# ArduinoMegaShield3.net
KiCad netlist of a schematic drawn in EAGLE
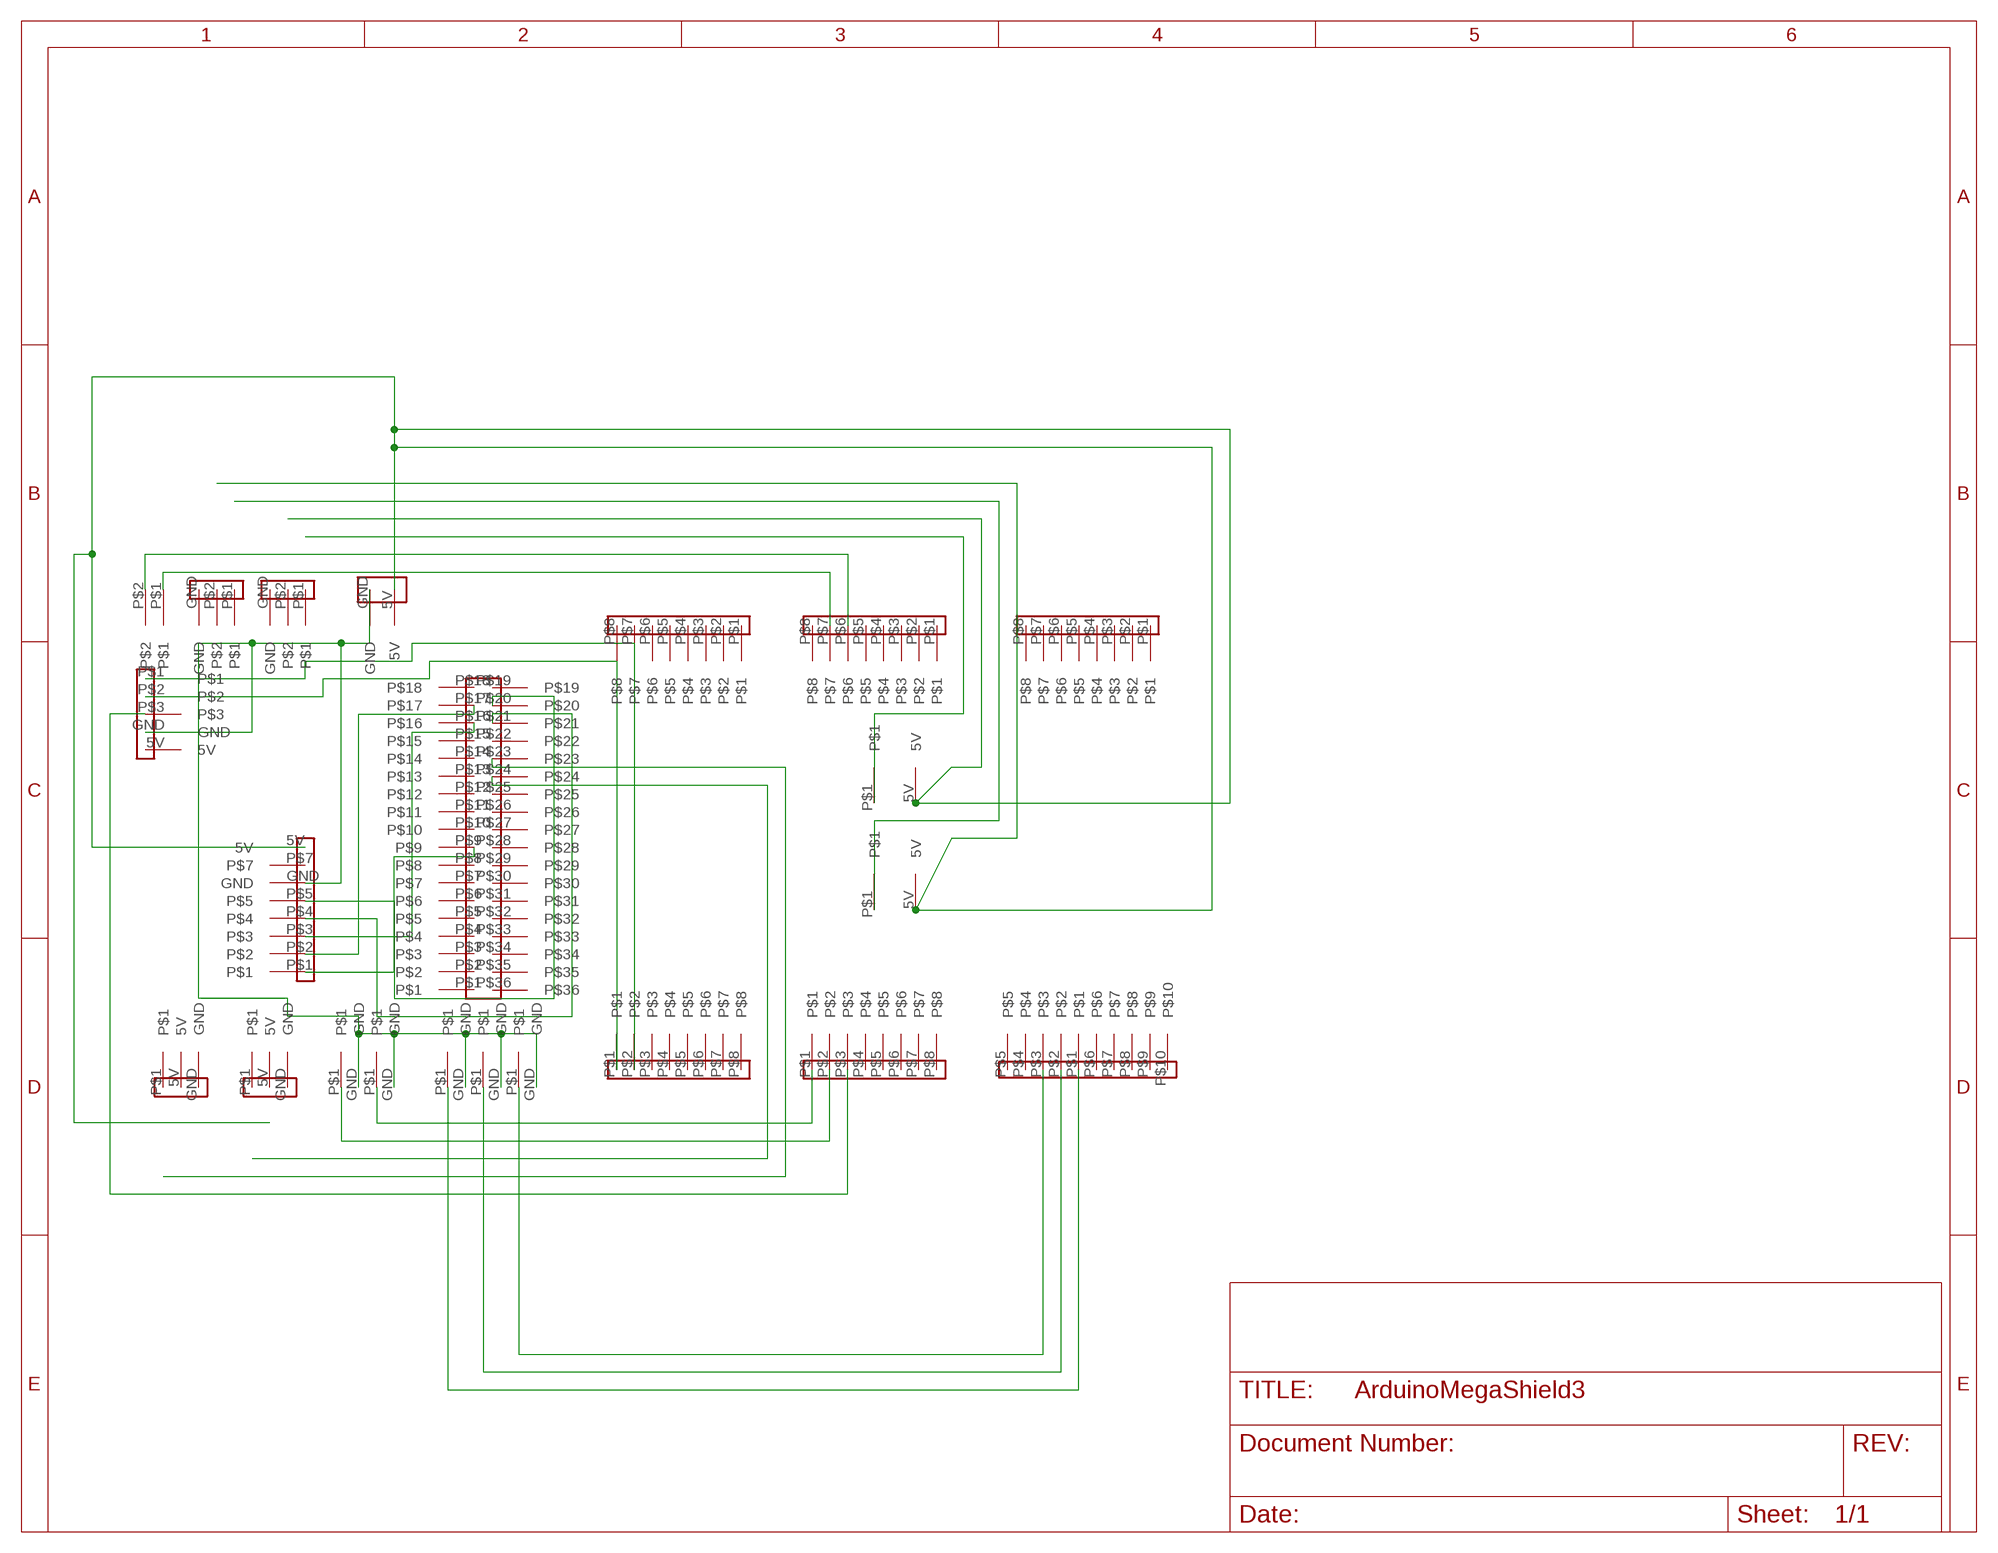
[diagram p0: schematic, sheet 1]

(export (version "E")
  (design (tool "Eeschema 10.0.6"))
  (components
    (comp (ref "U$1")
      (value "8PINHEADER2.54MM")
      (footprint "eagle-import:8PINHEADER2.54MM")
      (libsource (lib "eagle-import") (part "8PINHEADER2.54MM"))
    )
    (comp (ref "U$2")
      (value "8PINHEADER2.54MM")
      (footprint "eagle-import:8PINHEADER2.54MM")
      (libsource (lib "eagle-import") (part "8PINHEADER2.54MM"))
    )
    (comp (ref "U$3")
      (value "8PINHEADER2.54MM")
      (footprint "eagle-import:8PINHEADER2.54MM")
      (libsource (lib "eagle-import") (part "8PINHEADER2.54MM"))
    )
    (comp (ref "U$4")
      (value "8PINHEADER2.54MM")
      (footprint "eagle-import:8PINHEADER2.54MM")
      (libsource (lib "eagle-import") (part "8PINHEADER2.54MM"))
    )
    (comp (ref "U$5")
      (value "8PINHEADER2.54MM")
      (footprint "eagle-import:8PINHEADER2.54MM")
      (libsource (lib "eagle-import") (part "8PINHEADER2.54MM"))
    )
    (comp (ref "U$6")
      (value "10PINHEADER2.54MM")
      (footprint "eagle-import:10PINHEADER2.54MM")
      (libsource (lib "eagle-import") (part "10PINHEADER2.54MM"))
    )
    (comp (ref "U$7")
      (value "18X2HEADER2.54MM")
      (footprint "eagle-import:18X2HEADER2.54MM")
      (libsource (lib "eagle-import") (part "18X2HEADER2.54MM"))
    )
    (comp (ref "U$8")
      (value "5PINHEADER2.54MM")
      (footprint "eagle-import:5PINHEADER2.54MM")
      (libsource (lib "eagle-import") (part "5PINHEADER2.54MM"))
    )
    (comp (ref "U$9")
      (value "SERVOS")
      (footprint "eagle-import:SERVOS")
      (libsource (lib "eagle-import") (part "SERVOS"))
    )
    (comp (ref "U$10")
      (value "SDCARDMODULE")
      (footprint "eagle-import:SDCARDMODULE")
      (libsource (lib "eagle-import") (part "SDCARDMODULE"))
    )
    (comp (ref "U$11")
      (value "SERVOS")
      (footprint "eagle-import:SERVOS")
      (libsource (lib "eagle-import") (part "SERVOS"))
    )
    (comp (ref "U$12")
      (value "HALLEFFECTSENSORS")
      (footprint "eagle-import:HALLEFFECTSENSORS")
      (libsource (lib "eagle-import") (part "HALLEFFECTSENSORS"))
    )
    (comp (ref "U$13")
      (value "HALLEFFECTSENSORS")
      (footprint "eagle-import:HALLEFFECTSENSORS")
      (libsource (lib "eagle-import") (part "HALLEFFECTSENSORS"))
    )
    (comp (ref "U$14")
      (value "2PIN2.54MM")
      (footprint "eagle-import:2PIN2.54MM")
      (libsource (lib "eagle-import") (part "2PIN2.54MM"))
    )
    (comp (ref "U$15")
      (value "2PIN2.54MM")
      (footprint "eagle-import:2PIN2.54MM")
      (libsource (lib "eagle-import") (part "2PIN2.54MM"))
    )
    (comp (ref "U$17")
      (value "2PIN2.54MM")
      (footprint "eagle-import:2PIN2.54MM")
      (libsource (lib "eagle-import") (part "2PIN2.54MM"))
    )
    (comp (ref "U$18")
      (value "2PIN2.54MM")
      (footprint "eagle-import:2PIN2.54MM")
      (libsource (lib "eagle-import") (part "2PIN2.54MM"))
    )
    (comp (ref "U$19")
      (value "2PIN2.54MM")
      (footprint "eagle-import:2PIN2.54MM")
      (libsource (lib "eagle-import") (part "2PIN2.54MM"))
    )
    (comp (ref "U$20")
      (value "2PIN11MM")
      (footprint "eagle-import:2PIN11MM")
      (libsource (lib "eagle-import") (part "2PIN11MM"))
    )
    (comp (ref "U$21")
      (value "2PIN11MM")
      (footprint "eagle-import:2PIN11MM")
      (libsource (lib "eagle-import") (part "2PIN11MM"))
    )
    (comp (ref "U$22")
      (value "BUTTONS")
      (footprint "eagle-import:BUTTONS")
      (libsource (lib "eagle-import") (part "BUTTONS"))
    )
    (comp (ref "U$23")
      (value "2PINTERMINAL3.5MM")
      (footprint "eagle-import:2PINTERMINAL3.5MM")
      (libsource (lib "eagle-import") (part "2PINTERMINAL3.5MM"))
    )
  )
  (nets
    (net (code "1") (name "Net-(U$1-PadP$1)") (class "Default")
      (node (ref "U$1") (pin "P$1") (pinfunction "P$1_P$1") (pintype "bidirectional"))
      (node (ref "U$15") (pin "P$1") (pinfunction "P$1_P$1") (pintype "bidirectional"))
    )
    (net (code "2") (name "Net-(U$1-PadP$2)") (class "Default")
      (node (ref "U$1") (pin "P$2") (pinfunction "P$2_P$2") (pintype "bidirectional"))
      (node (ref "U$14") (pin "P$1") (pinfunction "P$1_P$1") (pintype "bidirectional"))
    )
    (net (code "3") (name "Net-(U$1-PadP$3)") (class "Default")
      (node (ref "U$1") (pin "P$3") (pinfunction "P$3_P$3") (pintype "bidirectional"))
      (node (ref "U$8") (pin "P$3") (pinfunction "P$3_P$3") (pintype "bidirectional"))
    )
    (net (code "4") (name "Net-(U$2-PadP$1)") (class "Default")
      (node (ref "U$2") (pin "P$1") (pinfunction "P$1_P$1") (pintype "bidirectional"))
      (node (ref "U$8") (pin "P$2") (pinfunction "P$2_P$2") (pintype "bidirectional"))
    )
    (net (code "5") (name "Net-(U$2-PadP$2)") (class "Default")
      (node (ref "U$2") (pin "P$2") (pinfunction "P$2_P$2") (pintype "bidirectional"))
      (node (ref "U$8") (pin "P$1") (pinfunction "P$1_P$1") (pintype "bidirectional"))
    )
    (net (code "6") (name "Net-(U$10-Pad5V)") (class "Default")
      (node (ref "U$10") (pin "5V") (pinfunction "5V_5V") (pintype "bidirectional"))
      (node (ref "U$20") (pin "5V") (pinfunction "5V_5V") (pintype "bidirectional"))
      (node (ref "U$21") (pin "5V") (pinfunction "5V_5V") (pintype "bidirectional"))
      (node (ref "U$23") (pin "5V") (pinfunction "5V_5V") (pintype "bidirectional"))
    )
    (net (code "7") (name "Net-(U$10-PadGND)") (class "Default")
      (node (ref "U$10") (pin "GND") (pinfunction "GND_GND") (pintype "bidirectional"))
      (node (ref "U$14") (pin "GND") (pinfunction "GND_GND") (pintype "bidirectional"))
      (node (ref "U$15") (pin "GND") (pinfunction "GND_GND") (pintype "bidirectional"))
      (node (ref "U$17") (pin "GND") (pinfunction "GND_GND") (pintype "bidirectional"))
      (node (ref "U$18") (pin "GND") (pinfunction "GND_GND") (pintype "bidirectional"))
      (node (ref "U$19") (pin "GND") (pinfunction "GND_GND") (pintype "bidirectional"))
      (node (ref "U$23") (pin "GND") (pinfunction "GND_GND") (pintype "bidirectional"))
      (node (ref "U$8") (pin "GND") (pinfunction "GND_GND") (pintype "bidirectional"))
    )
    (net (code "8") (name "Net-(U$10-PadP$1)") (class "Default")
      (node (ref "U$10") (pin "P$1") (pinfunction "P$1_P$1") (pintype "bidirectional"))
      (node (ref "U$7") (pin "P$9") (pinfunction "P$9_P$9") (pintype "bidirectional"))
    )
    (net (code "9") (name "Net-(U$10-PadP$2)") (class "Default")
      (node (ref "U$10") (pin "P$2") (pinfunction "P$2_P$2") (pintype "bidirectional"))
      (node (ref "U$7") (pin "P$17") (pinfunction "P$17_P$17") (pintype "bidirectional"))
    )
    (net (code "10") (name "Net-(U$10-PadP$3)") (class "Default")
      (node (ref "U$10") (pin "P$3") (pinfunction "P$3_P$3") (pintype "bidirectional"))
      (node (ref "U$7") (pin "P$16") (pinfunction "P$16_P$16") (pintype "bidirectional"))
    )
    (net (code "11") (name "Net-(U$10-PadP$4)") (class "Default")
      (node (ref "U$10") (pin "P$4") (pinfunction "P$4_P$4") (pintype "bidirectional"))
      (node (ref "U$7") (pin "P$21") (pinfunction "P$21_P$21") (pintype "bidirectional"))
    )
    (net (code "12") (name "Net-(U$10-PadP$5)") (class "Default")
      (node (ref "U$10") (pin "P$5") (pinfunction "P$5_P$5") (pintype "bidirectional"))
      (node (ref "U$7") (pin "P$20") (pinfunction "P$20_P$20") (pintype "bidirectional"))
    )
    (net (code "13") (name "Net-(U$17-PadP$1)") (class "Default")
      (node (ref "U$17") (pin "P$1") (pinfunction "P$1_P$1") (pintype "bidirectional"))
      (node (ref "U$6") (pin "P$1") (pinfunction "P$1_P$1") (pintype "bidirectional"))
    )
    (net (code "14") (name "Net-(U$18-PadP$1)") (class "Default")
      (node (ref "U$18") (pin "P$1") (pinfunction "P$1_P$1") (pintype "bidirectional"))
      (node (ref "U$6") (pin "P$2") (pinfunction "P$2_P$2") (pintype "bidirectional"))
    )
    (net (code "15") (name "Net-(U$19-PadP$1)") (class "Default")
      (node (ref "U$19") (pin "P$1") (pinfunction "P$1_P$1") (pintype "bidirectional"))
      (node (ref "U$6") (pin "P$3") (pinfunction "P$3_P$3") (pintype "bidirectional"))
    )
    (net (code "16") (name "Net-(U$22-PadP$1)") (class "Default")
      (node (ref "U$22") (pin "P$1") (pinfunction "P$1_P$1") (pintype "bidirectional"))
      (node (ref "U$4") (pin "P$7") (pinfunction "P$7_P$7") (pintype "bidirectional"))
    )
    (net (code "17") (name "Net-(U$22-PadP$2)") (class "Default")
      (node (ref "U$22") (pin "P$2") (pinfunction "P$2_P$2") (pintype "bidirectional"))
      (node (ref "U$4") (pin "P$6") (pinfunction "P$6_P$6") (pintype "bidirectional"))
    )
    (net (code "18") (name "unconnected-(U$1-PadP$4)") (class "Default")
      (node (ref "U$1") (pin "P$4") (pinfunction "P$4_P$4") (pintype "bidirectional"))
    )
    (net (code "19") (name "unconnected-(U$1-PadP$5)") (class "Default")
      (node (ref "U$1") (pin "P$5") (pinfunction "P$5_P$5") (pintype "bidirectional"))
    )
    (net (code "20") (name "unconnected-(U$1-PadP$6)") (class "Default")
      (node (ref "U$1") (pin "P$6") (pinfunction "P$6_P$6") (pintype "bidirectional"))
    )
    (net (code "21") (name "unconnected-(U$1-PadP$7)") (class "Default")
      (node (ref "U$1") (pin "P$7") (pinfunction "P$7_P$7") (pintype "bidirectional"))
    )
    (net (code "22") (name "unconnected-(U$1-PadP$8)") (class "Default")
      (node (ref "U$1") (pin "P$8") (pinfunction "P$8_P$8") (pintype "bidirectional"))
    )
    (net (code "23") (name "unconnected-(U$2-PadP$3)") (class "Default")
      (node (ref "U$2") (pin "P$3") (pinfunction "P$3_P$3") (pintype "bidirectional"))
    )
    (net (code "24") (name "unconnected-(U$2-PadP$4)") (class "Default")
      (node (ref "U$2") (pin "P$4") (pinfunction "P$4_P$4") (pintype "bidirectional"))
    )
    (net (code "25") (name "unconnected-(U$2-PadP$5)") (class "Default")
      (node (ref "U$2") (pin "P$5") (pinfunction "P$5_P$5") (pintype "bidirectional"))
    )
    (net (code "26") (name "unconnected-(U$2-PadP$6)") (class "Default")
      (node (ref "U$2") (pin "P$6") (pinfunction "P$6_P$6") (pintype "bidirectional"))
    )
    (net (code "27") (name "unconnected-(U$2-PadP$7)") (class "Default")
      (node (ref "U$2") (pin "P$7") (pinfunction "P$7_P$7") (pintype "bidirectional"))
    )
    (net (code "28") (name "unconnected-(U$2-PadP$8)") (class "Default")
      (node (ref "U$2") (pin "P$8") (pinfunction "P$8_P$8") (pintype "bidirectional"))
    )
    (net (code "29") (name "unconnected-(U$3-PadP$1)") (class "Default")
      (node (ref "U$3") (pin "P$1") (pinfunction "P$1_P$1") (pintype "bidirectional"))
    )
    (net (code "30") (name "unconnected-(U$3-PadP$2)") (class "Default")
      (node (ref "U$3") (pin "P$2") (pinfunction "P$2_P$2") (pintype "bidirectional"))
    )
    (net (code "31") (name "unconnected-(U$3-PadP$3)") (class "Default")
      (node (ref "U$3") (pin "P$3") (pinfunction "P$3_P$3") (pintype "bidirectional"))
    )
    (net (code "32") (name "unconnected-(U$3-PadP$4)") (class "Default")
      (node (ref "U$3") (pin "P$4") (pinfunction "P$4_P$4") (pintype "bidirectional"))
    )
    (net (code "33") (name "unconnected-(U$3-PadP$5)") (class "Default")
      (node (ref "U$3") (pin "P$5") (pinfunction "P$5_P$5") (pintype "bidirectional"))
    )
    (net (code "34") (name "unconnected-(U$3-PadP$6)") (class "Default")
      (node (ref "U$3") (pin "P$6") (pinfunction "P$6_P$6") (pintype "bidirectional"))
    )
    (net (code "35") (name "unconnected-(U$3-PadP$7)") (class "Default")
      (node (ref "U$3") (pin "P$7") (pinfunction "P$7_P$7") (pintype "bidirectional"))
    )
    (net (code "36") (name "unconnected-(U$3-PadP$8)") (class "Default")
      (node (ref "U$3") (pin "P$8") (pinfunction "P$8_P$8") (pintype "bidirectional"))
    )
    (net (code "37") (name "unconnected-(U$4-PadP$1)") (class "Default")
      (node (ref "U$4") (pin "P$1") (pinfunction "P$1_P$1") (pintype "bidirectional"))
    )
    (net (code "38") (name "unconnected-(U$4-PadP$2)") (class "Default")
      (node (ref "U$4") (pin "P$2") (pinfunction "P$2_P$2") (pintype "bidirectional"))
    )
    (net (code "39") (name "unconnected-(U$4-PadP$3)") (class "Default")
      (node (ref "U$4") (pin "P$3") (pinfunction "P$3_P$3") (pintype "bidirectional"))
    )
    (net (code "40") (name "unconnected-(U$4-PadP$4)") (class "Default")
      (node (ref "U$4") (pin "P$4") (pinfunction "P$4_P$4") (pintype "bidirectional"))
    )
    (net (code "41") (name "unconnected-(U$4-PadP$5)") (class "Default")
      (node (ref "U$4") (pin "P$5") (pinfunction "P$5_P$5") (pintype "bidirectional"))
    )
    (net (code "42") (name "unconnected-(U$4-PadP$8)") (class "Default")
      (node (ref "U$4") (pin "P$8") (pinfunction "P$8_P$8") (pintype "bidirectional"))
    )
    (net (code "43") (name "unconnected-(U$5-PadP$1)") (class "Default")
      (node (ref "U$5") (pin "P$1") (pinfunction "P$1_P$1") (pintype "bidirectional"))
    )
    (net (code "44") (name "unconnected-(U$5-PadP$2)") (class "Default")
      (node (ref "U$5") (pin "P$2") (pinfunction "P$2_P$2") (pintype "bidirectional"))
    )
    (net (code "45") (name "unconnected-(U$5-PadP$3)") (class "Default")
      (node (ref "U$5") (pin "P$3") (pinfunction "P$3_P$3") (pintype "bidirectional"))
    )
    (net (code "46") (name "unconnected-(U$5-PadP$4)") (class "Default")
      (node (ref "U$5") (pin "P$4") (pinfunction "P$4_P$4") (pintype "bidirectional"))
    )
    (net (code "47") (name "unconnected-(U$5-PadP$5)") (class "Default")
      (node (ref "U$5") (pin "P$5") (pinfunction "P$5_P$5") (pintype "bidirectional"))
    )
    (net (code "48") (name "unconnected-(U$5-PadP$6)") (class "Default")
      (node (ref "U$5") (pin "P$6") (pinfunction "P$6_P$6") (pintype "bidirectional"))
    )
    (net (code "49") (name "unconnected-(U$5-PadP$7)") (class "Default")
      (node (ref "U$5") (pin "P$7") (pinfunction "P$7_P$7") (pintype "bidirectional"))
    )
    (net (code "50") (name "unconnected-(U$5-PadP$8)") (class "Default")
      (node (ref "U$5") (pin "P$8") (pinfunction "P$8_P$8") (pintype "bidirectional"))
    )
    (net (code "51") (name "unconnected-(U$6-PadP$4)") (class "Default")
      (node (ref "U$6") (pin "P$4") (pinfunction "P$4_P$4") (pintype "bidirectional"))
    )
    (net (code "52") (name "unconnected-(U$6-PadP$5)") (class "Default")
      (node (ref "U$6") (pin "P$5") (pinfunction "P$5_P$5") (pintype "bidirectional"))
    )
    (net (code "53") (name "unconnected-(U$6-PadP$6)") (class "Default")
      (node (ref "U$6") (pin "P$6") (pinfunction "P$6_P$6") (pintype "bidirectional"))
    )
    (net (code "54") (name "unconnected-(U$6-PadP$7)") (class "Default")
      (node (ref "U$6") (pin "P$7") (pinfunction "P$7_P$7") (pintype "bidirectional"))
    )
    (net (code "55") (name "unconnected-(U$6-PadP$8)") (class "Default")
      (node (ref "U$6") (pin "P$8") (pinfunction "P$8_P$8") (pintype "bidirectional"))
    )
    (net (code "56") (name "unconnected-(U$6-PadP$9)") (class "Default")
      (node (ref "U$6") (pin "P$9") (pinfunction "P$9_P$9") (pintype "bidirectional"))
    )
    (net (code "57") (name "unconnected-(U$6-PadP$10)") (class "Default")
      (node (ref "U$6") (pin "P$10") (pinfunction "P$10_P$10") (pintype "bidirectional"))
    )
    (net (code "58") (name "unconnected-(U$7-PadP$1)") (class "Default")
      (node (ref "U$7") (pin "P$1") (pinfunction "P$1_P$1") (pintype "bidirectional"))
    )
    (net (code "59") (name "unconnected-(U$7-PadP$2)") (class "Default")
      (node (ref "U$7") (pin "P$2") (pinfunction "P$2_P$2") (pintype "bidirectional"))
    )
    (net (code "60") (name "unconnected-(U$7-PadP$3)") (class "Default")
      (node (ref "U$7") (pin "P$3") (pinfunction "P$3_P$3") (pintype "bidirectional"))
    )
    (net (code "61") (name "unconnected-(U$7-PadP$4)") (class "Default")
      (node (ref "U$7") (pin "P$4") (pinfunction "P$4_P$4") (pintype "bidirectional"))
    )
    (net (code "62") (name "unconnected-(U$7-PadP$5)") (class "Default")
      (node (ref "U$7") (pin "P$5") (pinfunction "P$5_P$5") (pintype "bidirectional"))
    )
    (net (code "63") (name "unconnected-(U$7-PadP$6)") (class "Default")
      (node (ref "U$7") (pin "P$6") (pinfunction "P$6_P$6") (pintype "bidirectional"))
    )
    (net (code "64") (name "unconnected-(U$7-PadP$7)") (class "Default")
      (node (ref "U$7") (pin "P$7") (pinfunction "P$7_P$7") (pintype "bidirectional"))
    )
    (net (code "65") (name "unconnected-(U$7-PadP$8)") (class "Default")
      (node (ref "U$7") (pin "P$8") (pinfunction "P$8_P$8") (pintype "bidirectional"))
    )
    (net (code "66") (name "unconnected-(U$7-PadP$10)") (class "Default")
      (node (ref "U$7") (pin "P$10") (pinfunction "P$10_P$10") (pintype "bidirectional"))
    )
    (net (code "67") (name "unconnected-(U$7-PadP$11)") (class "Default")
      (node (ref "U$7") (pin "P$11") (pinfunction "P$11_P$11") (pintype "bidirectional"))
    )
    (net (code "68") (name "unconnected-(U$7-PadP$12)") (class "Default")
      (node (ref "U$7") (pin "P$12") (pinfunction "P$12_P$12") (pintype "bidirectional"))
    )
    (net (code "69") (name "unconnected-(U$7-PadP$13)") (class "Default")
      (node (ref "U$7") (pin "P$13") (pinfunction "P$13_P$13") (pintype "bidirectional"))
    )
    (net (code "70") (name "unconnected-(U$7-PadP$14)") (class "Default")
      (node (ref "U$7") (pin "P$14") (pinfunction "P$14_P$14") (pintype "bidirectional"))
    )
    (net (code "71") (name "unconnected-(U$7-PadP$15)") (class "Default")
      (node (ref "U$7") (pin "P$15") (pinfunction "P$15_P$15") (pintype "bidirectional"))
    )
    (net (code "72") (name "unconnected-(U$7-PadP$18)") (class "Default")
      (node (ref "U$7") (pin "P$18") (pinfunction "P$18_P$18") (pintype "bidirectional"))
    )
    (net (code "73") (name "unconnected-(U$7-PadP$19)") (class "Default")
      (node (ref "U$7") (pin "P$19") (pinfunction "P$19_P$19") (pintype "bidirectional"))
    )
    (net (code "74") (name "unconnected-(U$7-PadP$22)") (class "Default")
      (node (ref "U$7") (pin "P$22") (pinfunction "P$22_P$22") (pintype "bidirectional"))
    )
    (net (code "75") (name "unconnected-(U$7-PadP$23)") (class "Default")
      (node (ref "U$7") (pin "P$23") (pinfunction "P$23_P$23") (pintype "bidirectional"))
    )
    (net (code "76") (name "unconnected-(U$7-PadP$24)") (class "Default")
      (node (ref "U$7") (pin "P$24") (pinfunction "P$24_P$24") (pintype "bidirectional"))
    )
    (net (code "77") (name "unconnected-(U$7-PadP$25)") (class "Default")
      (node (ref "U$7") (pin "P$25") (pinfunction "P$25_P$25") (pintype "bidirectional"))
    )
    (net (code "78") (name "unconnected-(U$7-PadP$26)") (class "Default")
      (node (ref "U$7") (pin "P$26") (pinfunction "P$26_P$26") (pintype "bidirectional"))
    )
    (net (code "79") (name "unconnected-(U$7-PadP$27)") (class "Default")
      (node (ref "U$7") (pin "P$27") (pinfunction "P$27_P$27") (pintype "bidirectional"))
    )
    (net (code "80") (name "unconnected-(U$7-PadP$28)") (class "Default")
      (node (ref "U$7") (pin "P$28") (pinfunction "P$28_P$28") (pintype "bidirectional"))
    )
    (net (code "81") (name "unconnected-(U$7-PadP$29)") (class "Default")
      (node (ref "U$7") (pin "P$29") (pinfunction "P$29_P$29") (pintype "bidirectional"))
    )
    (net (code "82") (name "unconnected-(U$7-PadP$30)") (class "Default")
      (node (ref "U$7") (pin "P$30") (pinfunction "P$30_P$30") (pintype "bidirectional"))
    )
    (net (code "83") (name "unconnected-(U$7-PadP$31)") (class "Default")
      (node (ref "U$7") (pin "P$31") (pinfunction "P$31_P$31") (pintype "bidirectional"))
    )
    (net (code "84") (name "unconnected-(U$7-PadP$32)") (class "Default")
      (node (ref "U$7") (pin "P$32") (pinfunction "P$32_P$32") (pintype "bidirectional"))
    )
    (net (code "85") (name "unconnected-(U$7-PadP$33)") (class "Default")
      (node (ref "U$7") (pin "P$33") (pinfunction "P$33_P$33") (pintype "bidirectional"))
    )
    (net (code "86") (name "unconnected-(U$7-PadP$34)") (class "Default")
      (node (ref "U$7") (pin "P$34") (pinfunction "P$34_P$34") (pintype "bidirectional"))
    )
    (net (code "87") (name "unconnected-(U$7-PadP$35)") (class "Default")
      (node (ref "U$7") (pin "P$35") (pinfunction "P$35_P$35") (pintype "bidirectional"))
    )
    (net (code "88") (name "unconnected-(U$7-PadP$36)") (class "Default")
      (node (ref "U$7") (pin "P$36") (pinfunction "P$36_P$36") (pintype "bidirectional"))
    )
    (net (code "89") (name "unconnected-(U$8-Pad5V)") (class "Default")
      (node (ref "U$8") (pin "5V") (pinfunction "5V_5V") (pintype "bidirectional"))
    )
    (net (code "90") (name "unconnected-(U$9-Pad5V)") (class "Default")
      (node (ref "U$9") (pin "5V") (pinfunction "5V_5V") (pintype "bidirectional"))
    )
    (net (code "91") (name "unconnected-(U$9-PadGND)") (class "Default")
      (node (ref "U$9") (pin "GND") (pinfunction "GND_GND") (pintype "bidirectional"))
    )
    (net (code "92") (name "unconnected-(U$9-PadP$1)") (class "Default")
      (node (ref "U$9") (pin "P$1") (pinfunction "P$1_P$1") (pintype "bidirectional"))
    )
    (net (code "93") (name "unconnected-(U$10-PadP$7)") (class "Default")
      (node (ref "U$10") (pin "P$7") (pinfunction "P$7_P$7") (pintype "bidirectional"))
    )
    (net (code "94") (name "unconnected-(U$11-Pad5V)") (class "Default")
      (node (ref "U$11") (pin "5V") (pinfunction "5V_5V") (pintype "bidirectional"))
    )
    (net (code "95") (name "unconnected-(U$11-PadGND)") (class "Default")
      (node (ref "U$11") (pin "GND") (pinfunction "GND_GND") (pintype "bidirectional"))
    )
    (net (code "96") (name "unconnected-(U$11-PadP$1)") (class "Default")
      (node (ref "U$11") (pin "P$1") (pinfunction "P$1_P$1") (pintype "bidirectional"))
    )
    (net (code "97") (name "unconnected-(U$12-PadGND)") (class "Default")
      (node (ref "U$12") (pin "GND") (pinfunction "GND_GND") (pintype "bidirectional"))
    )
    (net (code "98") (name "unconnected-(U$12-PadP$1)") (class "Default")
      (node (ref "U$12") (pin "P$1") (pinfunction "P$1_P$1") (pintype "bidirectional"))
    )
    (net (code "99") (name "unconnected-(U$12-PadP$2)") (class "Default")
      (node (ref "U$12") (pin "P$2") (pinfunction "P$2_P$2") (pintype "bidirectional"))
    )
    (net (code "100") (name "unconnected-(U$13-PadGND)") (class "Default")
      (node (ref "U$13") (pin "GND") (pinfunction "GND_GND") (pintype "bidirectional"))
    )
    (net (code "101") (name "unconnected-(U$13-PadP$1)") (class "Default")
      (node (ref "U$13") (pin "P$1") (pinfunction "P$1_P$1") (pintype "bidirectional"))
    )
    (net (code "102") (name "unconnected-(U$13-PadP$2)") (class "Default")
      (node (ref "U$13") (pin "P$2") (pinfunction "P$2_P$2") (pintype "bidirectional"))
    )
    (net (code "103") (name "unconnected-(U$20-PadP$1)") (class "Default")
      (node (ref "U$20") (pin "P$1") (pinfunction "P$1_P$1") (pintype "bidirectional"))
    )
    (net (code "104") (name "unconnected-(U$21-PadP$1)") (class "Default")
      (node (ref "U$21") (pin "P$1") (pinfunction "P$1_P$1") (pintype "bidirectional"))
    )
  )
)
